# T14_SuperDuper_V_006.net
KiCad netlist of a schematic drawn in EAGLE
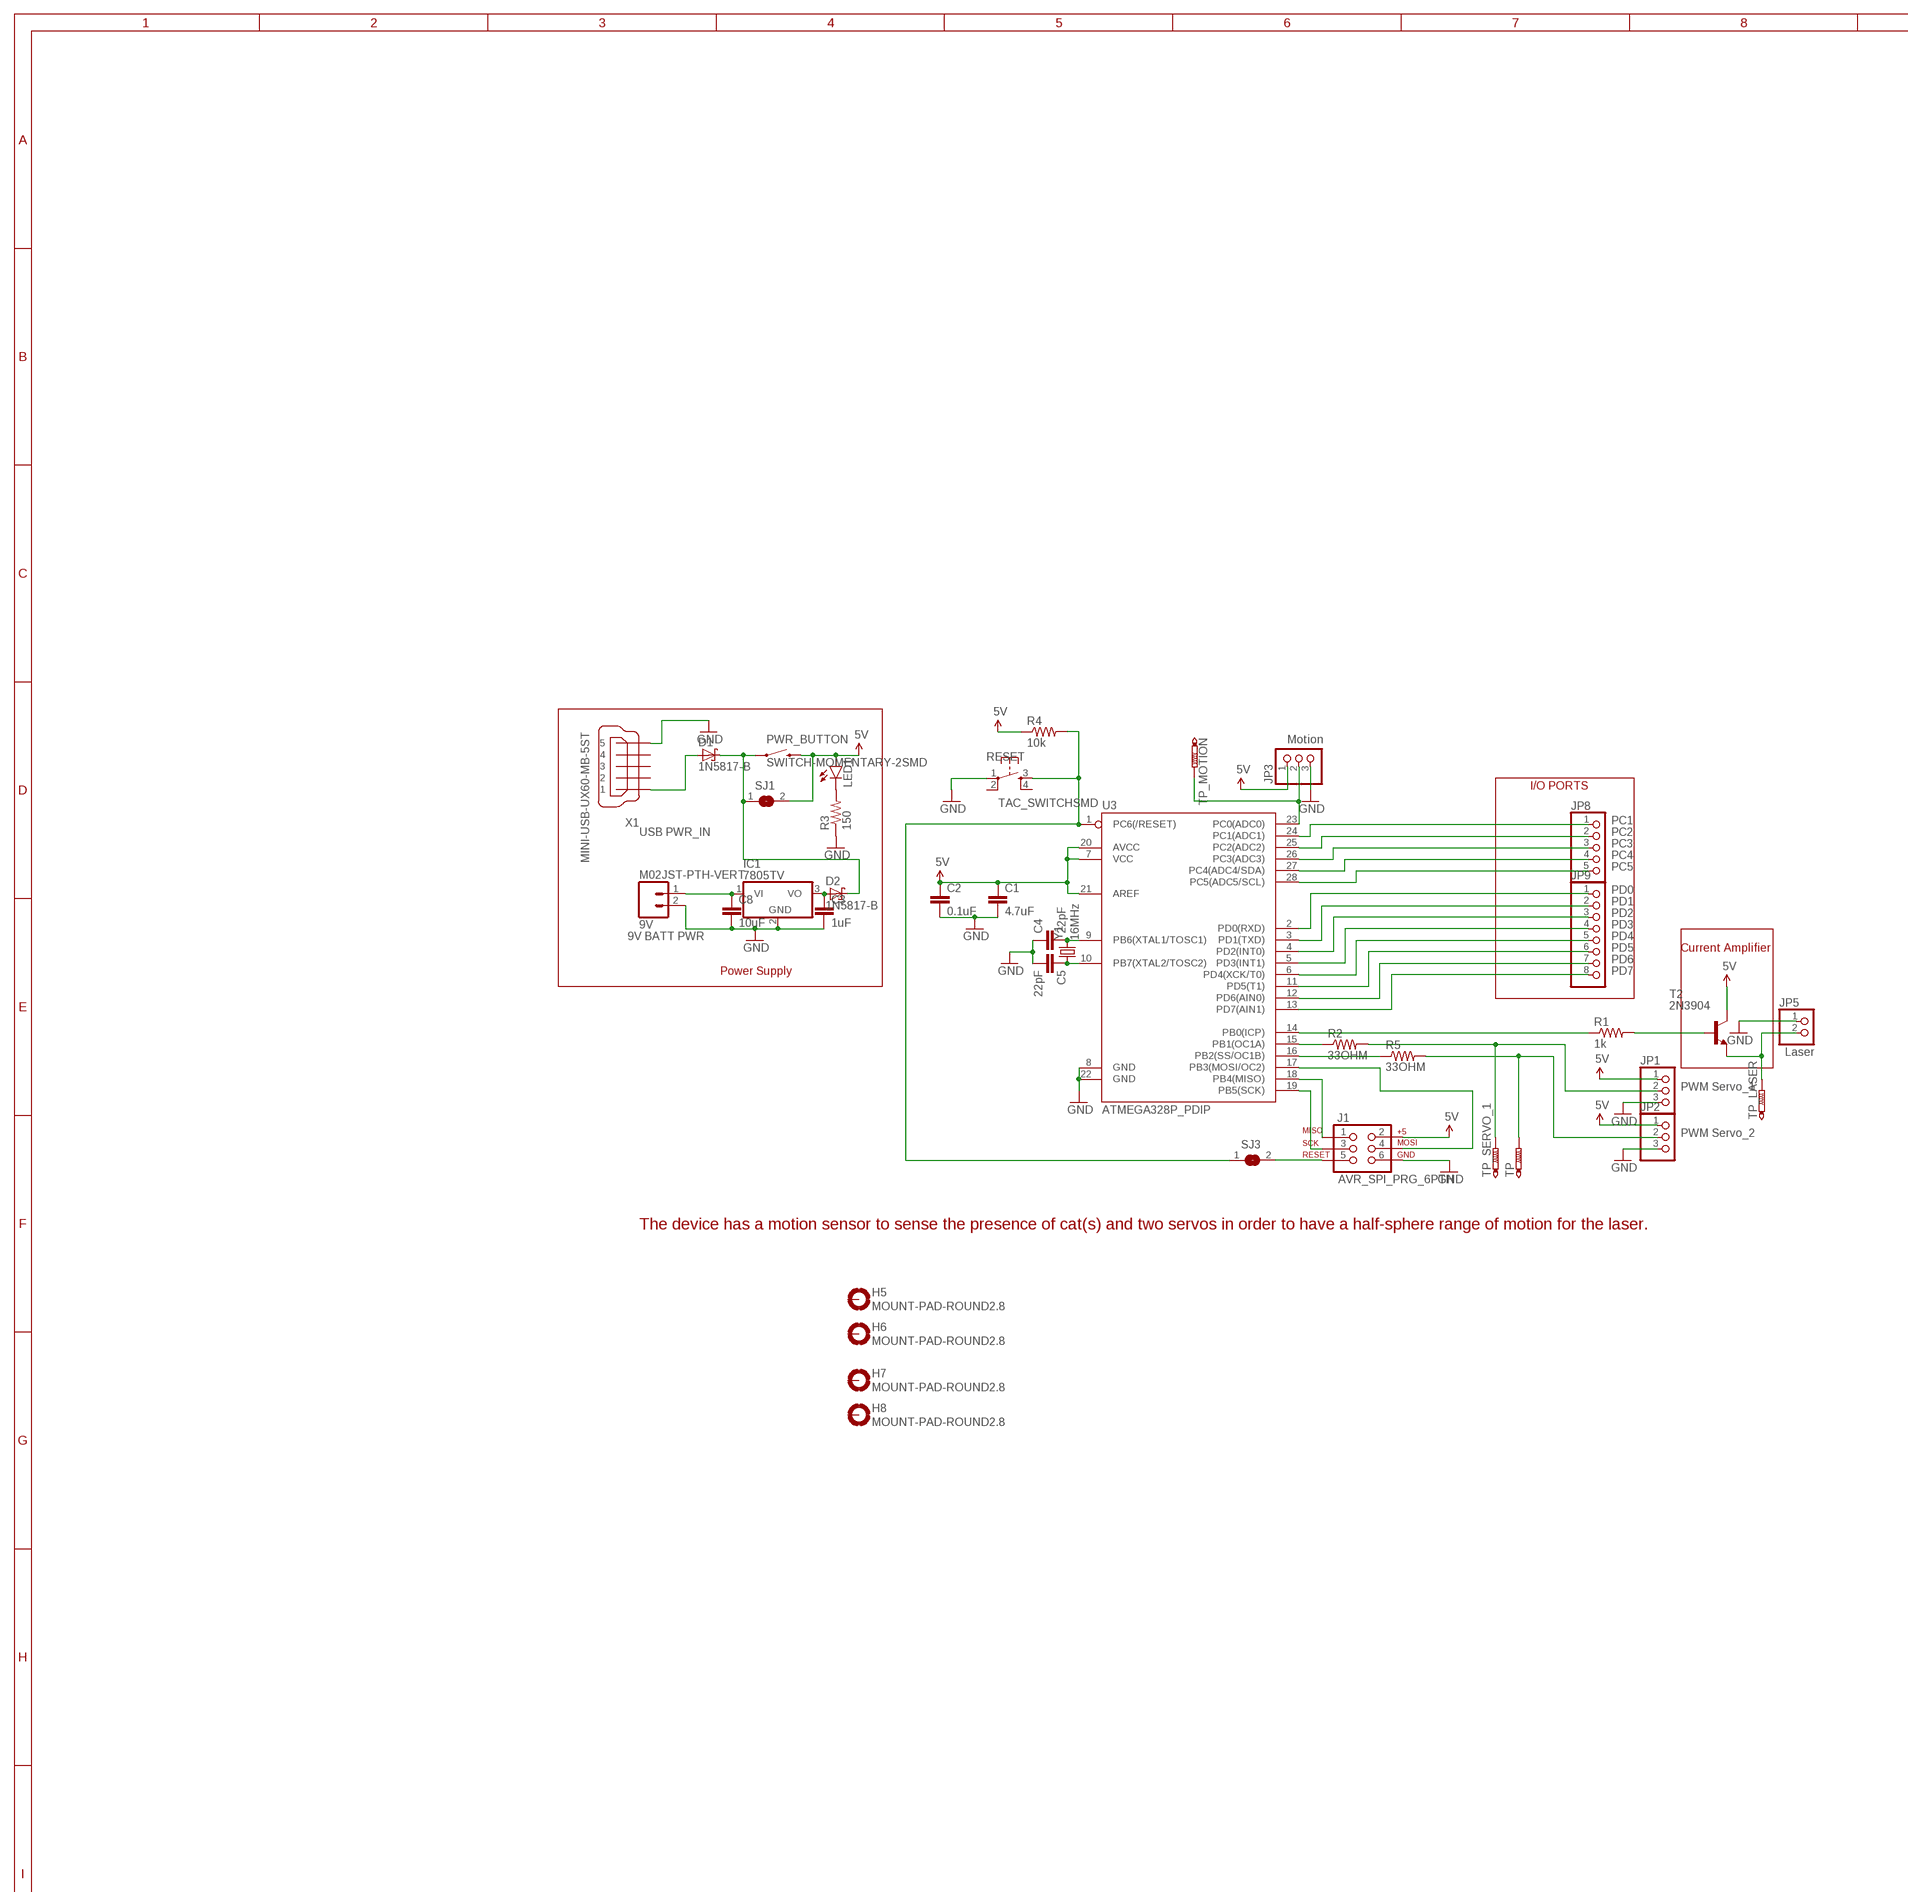
[diagram p0: schematic, sheet 1, part 1 of 2]
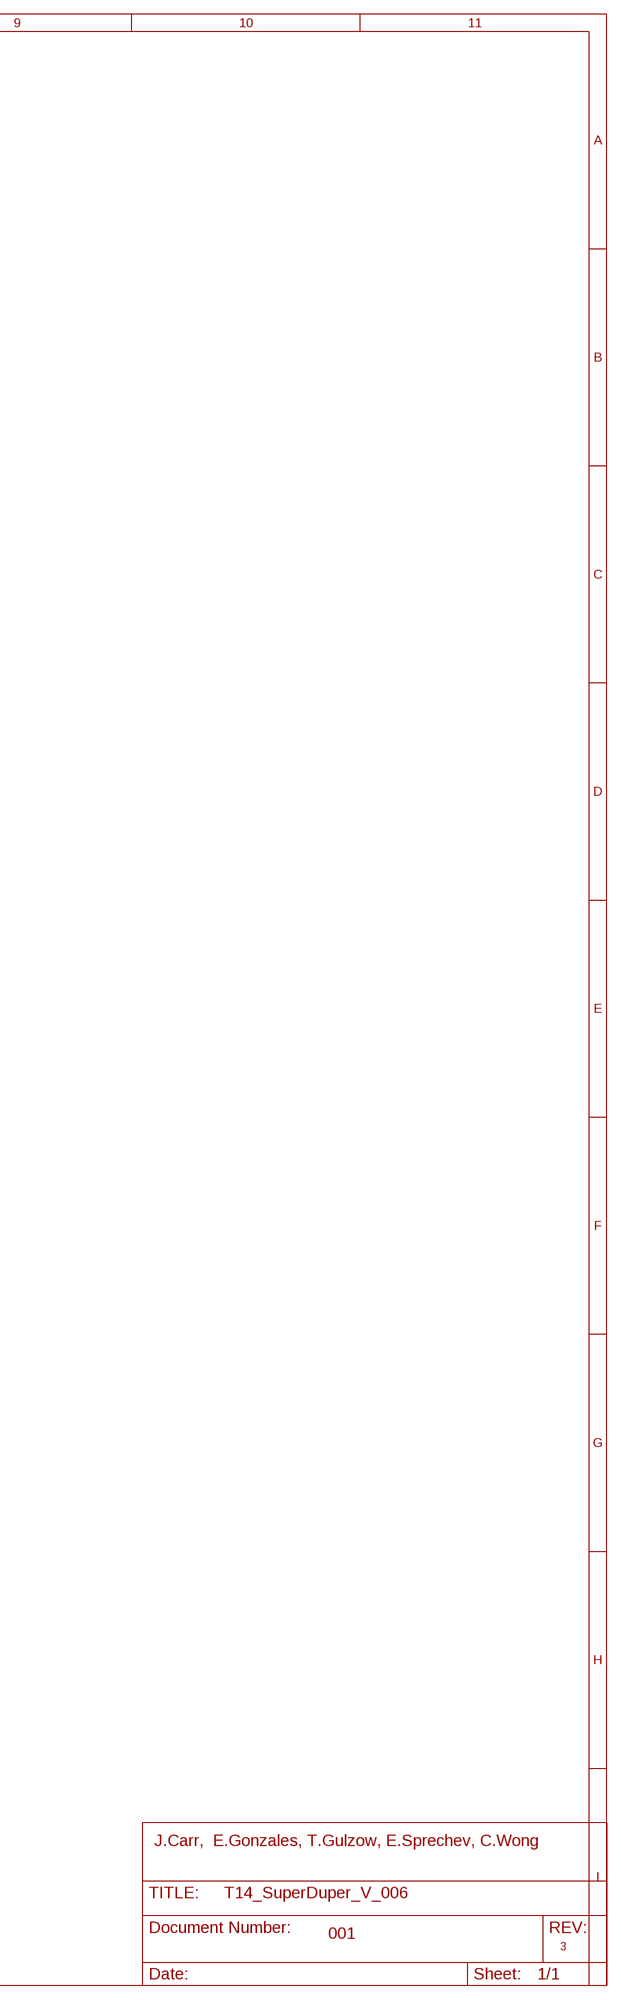
[diagram p1: schematic, sheet 1, part 2 of 2]

(export (version "E")
  (design (tool "Eeschema 10.0.6"))
  (components
    (comp (ref "9V")
      (value "M02JST-PTH-VERT")
      (footprint "eagle-import:JST-2-PTH-VERT")
      (libsource (lib "eagle-import") (part "M02JST-PTH-VERT"))
    )
    (comp (ref "C1")
      (value "4.7uF")
      (footprint "eagle-import:0603-CAP")
      (libsource (lib "eagle-import") (part "4.7UF-6.3V-10%(0603)0603"))
    )
    (comp (ref "C2")
      (value "0.1uF")
      (footprint "eagle-import:0603-CAP")
      (libsource (lib "eagle-import") (part "0.1UF-25V(+80/-20%)(0603)"))
    )
    (comp (ref "C3")
      (value "1uF")
      (footprint "eagle-import:0603-CAP")
      (fields (field (name "PROD_ID") "CAP-00810"))
      (libsource (lib "eagle-import") (part "0.1UF-25V(+80/-20%)(0603)"))
    )
    (comp (ref "C4")
      (value "22pF")
      (footprint "eagle-import:0603-CAP")
      (libsource (lib "eagle-import") (part "4.7UF-6.3V-10%(0603)0603"))
    )
    (comp (ref "C5")
      (value "22pF")
      (footprint "eagle-import:0603-CAP")
      (libsource (lib "eagle-import") (part "4.7UF-6.3V-10%(0603)0603"))
    )
    (comp (ref "C8")
      (value "10uF")
      (footprint "eagle-import:0603-CAP")
      (fields (field (name "PROD_ID") "CAP-00810"))
      (libsource (lib "eagle-import") (part "0.1UF-25V(+80/-20%)(0603)"))
    )
    (comp (ref "D1")
      (value "1N5817-B")
      (footprint "eagle-import:DO41-7.6")
      (libsource (lib "eagle-import") (part "1N5817-B"))
    )
    (comp (ref "D2")
      (value "1N5817-B")
      (footprint "eagle-import:DO41-7.6")
      (libsource (lib "eagle-import") (part "1N5817-B"))
    )
    (comp (ref "H5")
      (value "MOUNT-PAD-ROUND2.8")
      (footprint "eagle-import:2,8-PAD")
      (libsource (lib "eagle-import") (part "MOUNT-PAD-ROUND2.8"))
    )
    (comp (ref "H6")
      (value "MOUNT-PAD-ROUND2.8")
      (footprint "eagle-import:2,8-PAD")
      (libsource (lib "eagle-import") (part "MOUNT-PAD-ROUND2.8"))
    )
    (comp (ref "H7")
      (value "MOUNT-PAD-ROUND2.8")
      (footprint "eagle-import:2,8-PAD")
      (libsource (lib "eagle-import") (part "MOUNT-PAD-ROUND2.8"))
    )
    (comp (ref "H8")
      (value "MOUNT-PAD-ROUND2.8")
      (footprint "eagle-import:2,8-PAD")
      (libsource (lib "eagle-import") (part "MOUNT-PAD-ROUND2.8"))
    )
    (comp (ref "IC1")
      (value "7805TV")
      (footprint "eagle-import:TO220V")
      (libsource (lib "eagle-import") (part "78TV05"))
    )
    (comp (ref "J1")
      (value "AVR_SPI_PRG_6PTH")
      (footprint "eagle-import:2X3")
      (libsource (lib "eagle-import") (part "AVR_SPI_PRG_6PTH"))
    )
    (comp (ref "JP1")
      (value "PINHD-1X3")
      (footprint "eagle-import:1X03")
      (libsource (lib "eagle-import") (part "PINHD-1X3"))
    )
    (comp (ref "JP2")
      (value "PINHD-1X3")
      (footprint "eagle-import:1X03")
      (libsource (lib "eagle-import") (part "PINHD-1X3"))
    )
    (comp (ref "JP3")
      (value "PINHD-1X3")
      (footprint "eagle-import:1X03")
      (libsource (lib "eagle-import") (part "PINHD-1X3"))
    )
    (comp (ref "JP5")
      (value "PINHD-1X2")
      (footprint "eagle-import:1X02")
      (libsource (lib "eagle-import") (part "PINHD-1X2"))
    )
    (comp (ref "JP8")
      (value "PINHD-1X5")
      (footprint "eagle-import:1X05")
      (libsource (lib "eagle-import") (part "PINHD-1X5"))
    )
    (comp (ref "JP9")
      (value "PINHD-1X8")
      (footprint "eagle-import:1X08")
      (libsource (lib "eagle-import") (part "PINHD-1X8"))
    )
    (comp (ref "LED1")
      (value "LED-3MM-NO_SILK")
      (footprint "eagle-import:LED3MM-NS")
      (libsource (lib "eagle-import") (part "LED-3MM-NO_SILK"))
    )
    (comp (ref "PWR_BUTTON")
      (value "SWITCH-MOMENTARY-2SMD")
      (footprint "eagle-import:TACTILE-SWITCH-SMD")
      (libsource (lib "eagle-import") (part "SWITCH-MOMENTARY-2SMD"))
    )
    (comp (ref "R1")
      (value "1k")
      (footprint "eagle-import:0603")
      (libsource (lib "eagle-import") (part "33OHM1/10W1%(0603)"))
    )
    (comp (ref "R2")
      (value "33OHM")
      (footprint "eagle-import:0603")
      (libsource (lib "eagle-import") (part "33OHM1/10W1%(0603)"))
    )
    (comp (ref "R3")
      (value "150")
      (footprint "eagle-import:0603")
      (libsource (lib "eagle-import") (part "33OHM1/10W1%(0603)"))
    )
    (comp (ref "R4")
      (value "10k")
      (footprint "eagle-import:0603")
      (libsource (lib "eagle-import") (part "33OHM1/10W1%(0603)"))
    )
    (comp (ref "R5")
      (value "33OHM")
      (footprint "eagle-import:0603")
      (libsource (lib "eagle-import") (part "33OHM1/10W1%(0603)"))
    )
    (comp (ref "RESET")
      (value "TAC_SWITCHSMD")
      (footprint "eagle-import:TACTILE-SWITCH-SMD")
      (libsource (lib "eagle-import") (part "TAC_SWITCHSMD"))
    )
    (comp (ref "SJ1") (value "SJ") (footprint "eagle-import:SJ") (libsource (lib "eagle-import") (part "SJ")))
    (comp (ref "SJ3") (value "SJ") (footprint "eagle-import:SJ") (libsource (lib "eagle-import") (part "SJ")))
    (comp (ref "T2")
      (value "2N3904")
      (footprint "eagle-import:TO92")
      (libsource (lib "eagle-import") (part "2N3904"))
    )
    (comp (ref "TP")
      (value "PTR1B2,54")
      (footprint "eagle-import:B2,54")
      (libsource (lib "eagle-import") (part "PTR1B2,54"))
    )
    (comp (ref "TP_LASER")
      (value "PTR1B2,54")
      (footprint "eagle-import:B2,54")
      (libsource (lib "eagle-import") (part "PTR1B2,54"))
    )
    (comp (ref "TP_MOTION")
      (value "PTR1B2,54")
      (footprint "eagle-import:B2,54")
      (libsource (lib "eagle-import") (part "PTR1B2,54"))
    )
    (comp (ref "TP_SERVO_1")
      (value "PTR1B2,54")
      (footprint "eagle-import:B2,54")
      (libsource (lib "eagle-import") (part "PTR1B2,54"))
    )
    (comp (ref "U3")
      (value "ATMEGA328P_PDIP")
      (footprint "eagle-import:DIL28-3")
      (libsource (lib "eagle-import") (part "ATMEGA328P_PDIP"))
    )
    (comp (ref "X1")
      (value "MINI-USB-UX60-MB-5ST")
      (footprint "eagle-import:UX60-MB-5ST")
      (libsource (lib "eagle-import") (part "MINI-USB-UX60-MB-5ST"))
    )
    (comp (ref "Y1")
      (value "16MHz")
      (footprint "eagle-import:CRYSTAL-SMD-10.5X4.8-2PIN")
      (libsource (lib "eagle-import") (part "CRYSTAL10.5X4.8"))
    )
  )
  (nets
    (net (code "1") (name "5V") (class "Default")
      (node (ref "C1") (pin "1") (pinfunction "1_1") (pintype "passive"))
      (node (ref "C2") (pin "1") (pinfunction "1_1") (pintype "passive"))
      (node (ref "J1") (pin "2") (pinfunction "2_2") (pintype "passive"))
      (node (ref "JP1") (pin "1") (pinfunction "1_1") (pintype "passive"))
      (node (ref "JP2") (pin "1") (pinfunction "1_1") (pintype "passive"))
      (node (ref "JP3") (pin "1") (pinfunction "1_1") (pintype "passive"))
      (node (ref "LED1") (pin "A") (pinfunction "A_A") (pintype "passive"))
      (node (ref "PWR_BUTTON") (pin "3") (pinfunction "2_3") (pintype "passive"))
      (node (ref "R4") (pin "1") (pinfunction "1_1") (pintype "passive"))
      (node (ref "SJ1") (pin "2") (pinfunction "2_2") (pintype "passive"))
      (node (ref "T2") (pin "1") (pinfunction "C_1") (pintype "passive"))
      (node (ref "U3") (pin "20") (pinfunction "AVCC_20") (pintype "bidirectional"))
      (node (ref "U3") (pin "21") (pinfunction "AREF_21") (pintype "bidirectional"))
      (node (ref "U3") (pin "7") (pinfunction "VCC_7") (pintype "bidirectional"))
    )
    (net (code "2") (name "GND") (class "Default")
      (node (ref "9V") (pin "2") (pinfunction "2_2") (pintype "passive"))
      (node (ref "C1") (pin "2") (pinfunction "2_2") (pintype "passive"))
      (node (ref "C2") (pin "2") (pinfunction "2_2") (pintype "passive"))
      (node (ref "C3") (pin "2") (pinfunction "2_2") (pintype "passive"))
      (node (ref "C4") (pin "1") (pinfunction "1_1") (pintype "passive"))
      (node (ref "C5") (pin "2") (pinfunction "2_2") (pintype "passive"))
      (node (ref "C8") (pin "2") (pinfunction "2_2") (pintype "passive"))
      (node (ref "IC1") (pin "2") (pinfunction "GND_2") (pintype "passive"))
      (node (ref "J1") (pin "6") (pinfunction "6_6") (pintype "passive"))
      (node (ref "JP1") (pin "3") (pinfunction "3_3") (pintype "passive"))
      (node (ref "JP2") (pin "3") (pinfunction "3_3") (pintype "passive"))
      (node (ref "JP3") (pin "3") (pinfunction "3_3") (pintype "passive"))
      (node (ref "JP5") (pin "1") (pinfunction "1_1") (pintype "passive"))
      (node (ref "R3") (pin "1") (pinfunction "1_1") (pintype "passive"))
      (node (ref "RESET") (pin "1") (pinfunction "1_1") (pintype "passive"))
      (node (ref "U3") (pin "22") (pinfunction "GND_22") (pintype "bidirectional"))
      (node (ref "U3") (pin "8") (pinfunction "GND_8") (pintype "bidirectional"))
      (node (ref "X1") (pin "5") (pinfunction "5_5") (pintype "input"))
    )
    (net (code "3") (name "Net-(D1-PadA)") (class "Default")
      (node (ref "D1") (pin "A") (pinfunction "A_A") (pintype "passive"))
      (node (ref "X1") (pin "1") (pinfunction "1_1") (pintype "input"))
    )
    (net (code "4") (name "Net-(D1-PadC)") (class "Default")
      (node (ref "D1") (pin "C") (pinfunction "C_C") (pintype "passive"))
      (node (ref "D2") (pin "C") (pinfunction "C_C") (pintype "passive"))
      (node (ref "PWR_BUTTON") (pin "1") (pinfunction "1_1") (pintype "passive"))
      (node (ref "SJ1") (pin "1") (pinfunction "1_1") (pintype "passive"))
    )
    (net (code "5") (name "Net-(IC1-VI)") (class "Default")
      (node (ref "9V") (pin "1") (pinfunction "1_1") (pintype "passive"))
      (node (ref "C8") (pin "1") (pinfunction "1_1") (pintype "passive"))
      (node (ref "IC1") (pin "1") (pinfunction "VI_1") (pintype "input"))
    )
    (net (code "6") (name "Net-(IC1-VO)") (class "Default")
      (node (ref "C3") (pin "1") (pinfunction "1_1") (pintype "passive"))
      (node (ref "D2") (pin "A") (pinfunction "A_A") (pintype "passive"))
      (node (ref "IC1") (pin "3") (pinfunction "VO_3") (pintype "passive"))
    )
    (net (code "7") (name "Net-(J1-Pad5)") (class "Default")
      (node (ref "J1") (pin "5") (pinfunction "5_5") (pintype "passive"))
      (node (ref "SJ3") (pin "2") (pinfunction "2_2") (pintype "passive"))
    )
    (net (code "8") (name "Net-(JP1-Pad2)") (class "Default")
      (node (ref "JP1") (pin "2") (pinfunction "2_2") (pintype "passive"))
      (node (ref "R2") (pin "2") (pinfunction "2_2") (pintype "passive"))
      (node (ref "TP_SERVO_1") (pin "TP") (pinfunction "TP_TP") (pintype "input"))
    )
    (net (code "9") (name "Net-(JP2-Pad2)") (class "Default")
      (node (ref "JP2") (pin "2") (pinfunction "2_2") (pintype "passive"))
      (node (ref "R5") (pin "2") (pinfunction "2_2") (pintype "passive"))
      (node (ref "TP") (pin "TP") (pinfunction "TP_TP") (pintype "input"))
    )
    (net (code "10") (name "Net-(LED1-C)") (class "Default")
      (node (ref "LED1") (pin "K") (pinfunction "C_K") (pintype "passive"))
      (node (ref "R3") (pin "2") (pinfunction "2_2") (pintype "passive"))
    )
    (net (code "11") (name "Net-(T2-B)") (class "Default")
      (node (ref "R1") (pin "2") (pinfunction "2_2") (pintype "passive"))
      (node (ref "T2") (pin "2") (pinfunction "B_2") (pintype "passive"))
    )
    (net (code "12") (name "Net-(T2-E)") (class "Default")
      (node (ref "JP5") (pin "2") (pinfunction "2_2") (pintype "passive"))
      (node (ref "T2") (pin "3") (pinfunction "E_3") (pintype "passive"))
      (node (ref "TP_LASER") (pin "TP") (pinfunction "TP_TP") (pintype "input"))
    )
    (net (code "13") (name "Net-(U3-PB0(ICP))") (class "Default")
      (node (ref "R1") (pin "1") (pinfunction "1_1") (pintype "passive"))
      (node (ref "U3") (pin "14") (pinfunction "PB0(ICP)_14") (pintype "bidirectional"))
    )
    (net (code "14") (name "Net-(U3-PB1(OC1A))") (class "Default")
      (node (ref "R2") (pin "1") (pinfunction "1_1") (pintype "passive"))
      (node (ref "U3") (pin "15") (pinfunction "PB1(OC1A)_15") (pintype "bidirectional"))
    )
    (net (code "15") (name "Net-(U3-PB2(SS{slash}OC1B))") (class "Default")
      (node (ref "R5") (pin "1") (pinfunction "1_1") (pintype "passive"))
      (node (ref "U3") (pin "16") (pinfunction "PB2(SS/OC1B)_16") (pintype "bidirectional"))
    )
    (net (code "16") (name "Net-(U3-PB3(MOSI{slash}OC2))") (class "Default")
      (node (ref "J1") (pin "4") (pinfunction "4_4") (pintype "passive"))
      (node (ref "U3") (pin "17") (pinfunction "PB3(MOSI/OC2)_17") (pintype "bidirectional"))
    )
    (net (code "17") (name "Net-(U3-PB4(MISO))") (class "Default")
      (node (ref "J1") (pin "1") (pinfunction "1_1") (pintype "passive"))
      (node (ref "U3") (pin "18") (pinfunction "PB4(MISO)_18") (pintype "bidirectional"))
    )
    (net (code "18") (name "Net-(U3-PB5(SCK))") (class "Default")
      (node (ref "J1") (pin "3") (pinfunction "3_3") (pintype "passive"))
      (node (ref "U3") (pin "19") (pinfunction "PB5(SCK)_19") (pintype "bidirectional"))
    )
    (net (code "19") (name "Net-(U3-PB6(XTAL1{slash}TOSC1))") (class "Default")
      (node (ref "C4") (pin "2") (pinfunction "2_2") (pintype "passive"))
      (node (ref "U3") (pin "9") (pinfunction "PB6(XTAL1/TOSC1)_9") (pintype "bidirectional"))
      (node (ref "Y1") (pin "P$2") (pinfunction "2_P$2") (pintype "passive"))
    )
    (net (code "20") (name "Net-(U3-PB7(XTAL2{slash}TOSC2))") (class "Default")
      (node (ref "C5") (pin "1") (pinfunction "1_1") (pintype "passive"))
      (node (ref "U3") (pin "10") (pinfunction "PB7(XTAL2/TOSC2)_10") (pintype "bidirectional"))
      (node (ref "Y1") (pin "P$1") (pinfunction "1_P$1") (pintype "passive"))
    )
    (net (code "21") (name "Net-(U3-PC0(ADC0))") (class "Default")
      (node (ref "JP3") (pin "2") (pinfunction "2_2") (pintype "passive"))
      (node (ref "TP_MOTION") (pin "TP") (pinfunction "TP_TP") (pintype "input"))
      (node (ref "U3") (pin "23") (pinfunction "PC0(ADC0)_23") (pintype "bidirectional"))
    )
    (net (code "22") (name "Net-(U3-PC1(ADC1))") (class "Default")
      (node (ref "JP8") (pin "1") (pinfunction "1_1") (pintype "passive"))
      (node (ref "U3") (pin "24") (pinfunction "PC1(ADC1)_24") (pintype "bidirectional"))
    )
    (net (code "23") (name "Net-(U3-PC2(ADC2))") (class "Default")
      (node (ref "JP8") (pin "2") (pinfunction "2_2") (pintype "passive"))
      (node (ref "U3") (pin "25") (pinfunction "PC2(ADC2)_25") (pintype "bidirectional"))
    )
    (net (code "24") (name "Net-(U3-PC3(ADC3))") (class "Default")
      (node (ref "JP8") (pin "3") (pinfunction "3_3") (pintype "passive"))
      (node (ref "U3") (pin "26") (pinfunction "PC3(ADC3)_26") (pintype "bidirectional"))
    )
    (net (code "25") (name "Net-(U3-PC4(ADC4{slash}SDA))") (class "Default")
      (node (ref "JP8") (pin "4") (pinfunction "4_4") (pintype "passive"))
      (node (ref "U3") (pin "27") (pinfunction "PC4(ADC4/SDA)_27") (pintype "bidirectional"))
    )
    (net (code "26") (name "Net-(U3-PC5(ADC5{slash}SCL))") (class "Default")
      (node (ref "JP8") (pin "5") (pinfunction "5_5") (pintype "passive"))
      (node (ref "U3") (pin "28") (pinfunction "PC5(ADC5/SCL)_28") (pintype "bidirectional"))
    )
    (net (code "27") (name "Net-(U3-PC6({slash}RESET))") (class "Default")
      (node (ref "R4") (pin "2") (pinfunction "2_2") (pintype "passive"))
      (node (ref "RESET") (pin "3") (pinfunction "3_3") (pintype "passive"))
      (node (ref "SJ3") (pin "1") (pinfunction "1_1") (pintype "passive"))
      (node (ref "U3") (pin "1") (pinfunction "PC6(/RESET)_1") (pintype "bidirectional"))
    )
    (net (code "28") (name "Net-(U3-PD0(RXD))") (class "Default")
      (node (ref "JP9") (pin "1") (pinfunction "1_1") (pintype "passive"))
      (node (ref "U3") (pin "2") (pinfunction "PD0(RXD)_2") (pintype "bidirectional"))
    )
    (net (code "29") (name "Net-(U3-PD1(TXD))") (class "Default")
      (node (ref "JP9") (pin "2") (pinfunction "2_2") (pintype "passive"))
      (node (ref "U3") (pin "3") (pinfunction "PD1(TXD)_3") (pintype "bidirectional"))
    )
    (net (code "30") (name "Net-(U3-PD2(INT0))") (class "Default")
      (node (ref "JP9") (pin "3") (pinfunction "3_3") (pintype "passive"))
      (node (ref "U3") (pin "4") (pinfunction "PD2(INT0)_4") (pintype "bidirectional"))
    )
    (net (code "31") (name "Net-(U3-PD3(INT1))") (class "Default")
      (node (ref "JP9") (pin "4") (pinfunction "4_4") (pintype "passive"))
      (node (ref "U3") (pin "5") (pinfunction "PD3(INT1)_5") (pintype "bidirectional"))
    )
    (net (code "32") (name "Net-(U3-PD4(XCK{slash}T0))") (class "Default")
      (node (ref "JP9") (pin "5") (pinfunction "5_5") (pintype "passive"))
      (node (ref "U3") (pin "6") (pinfunction "PD4(XCK/T0)_6") (pintype "bidirectional"))
    )
    (net (code "33") (name "Net-(U3-PD5(T1))") (class "Default")
      (node (ref "JP9") (pin "6") (pinfunction "6_6") (pintype "passive"))
      (node (ref "U3") (pin "11") (pinfunction "PD5(T1)_11") (pintype "bidirectional"))
    )
    (net (code "34") (name "Net-(U3-PD6(AIN0))") (class "Default")
      (node (ref "JP9") (pin "7") (pinfunction "7_7") (pintype "passive"))
      (node (ref "U3") (pin "12") (pinfunction "PD6(AIN0)_12") (pintype "bidirectional"))
    )
    (net (code "35") (name "Net-(U3-PD7(AIN1))") (class "Default")
      (node (ref "JP9") (pin "8") (pinfunction "8_8") (pintype "passive"))
      (node (ref "U3") (pin "13") (pinfunction "PD7(AIN1)_13") (pintype "bidirectional"))
    )
    (net (code "36") (name "unconnected-(H5-MOUNT-PadB2,8)") (class "Default")
      (node (ref "H5") (pin "B2,8") (pinfunction "MOUNT_B2,8") (pintype "passive"))
    )
    (net (code "37") (name "unconnected-(H6-MOUNT-PadB2,8)") (class "Default")
      (node (ref "H6") (pin "B2,8") (pinfunction "MOUNT_B2,8") (pintype "passive"))
    )
    (net (code "38") (name "unconnected-(H7-MOUNT-PadB2,8)") (class "Default")
      (node (ref "H7") (pin "B2,8") (pinfunction "MOUNT_B2,8") (pintype "passive"))
    )
    (net (code "39") (name "unconnected-(H8-MOUNT-PadB2,8)") (class "Default")
      (node (ref "H8") (pin "B2,8") (pinfunction "MOUNT_B2,8") (pintype "passive"))
    )
    (net (code "40") (name "unconnected-(RESET-Pad2)") (class "Default")
      (node (ref "RESET") (pin "2") (pinfunction "2_2") (pintype "passive"))
    )
    (net (code "41") (name "unconnected-(RESET-Pad4)") (class "Default")
      (node (ref "RESET") (pin "4") (pinfunction "4_4") (pintype "passive"))
    )
    (net (code "42") (name "unconnected-(X1-Pad2)") (class "Default")
      (node (ref "X1") (pin "2") (pinfunction "2_2") (pintype "input"))
    )
    (net (code "43") (name "unconnected-(X1-Pad3)") (class "Default")
      (node (ref "X1") (pin "3") (pinfunction "3_3") (pintype "input"))
    )
    (net (code "44") (name "unconnected-(X1-Pad4)") (class "Default")
      (node (ref "X1") (pin "4") (pinfunction "4_4") (pintype "input"))
    )
  )
)
